# Breakout.net
KiCad netlist of a schematic drawn in EAGLE
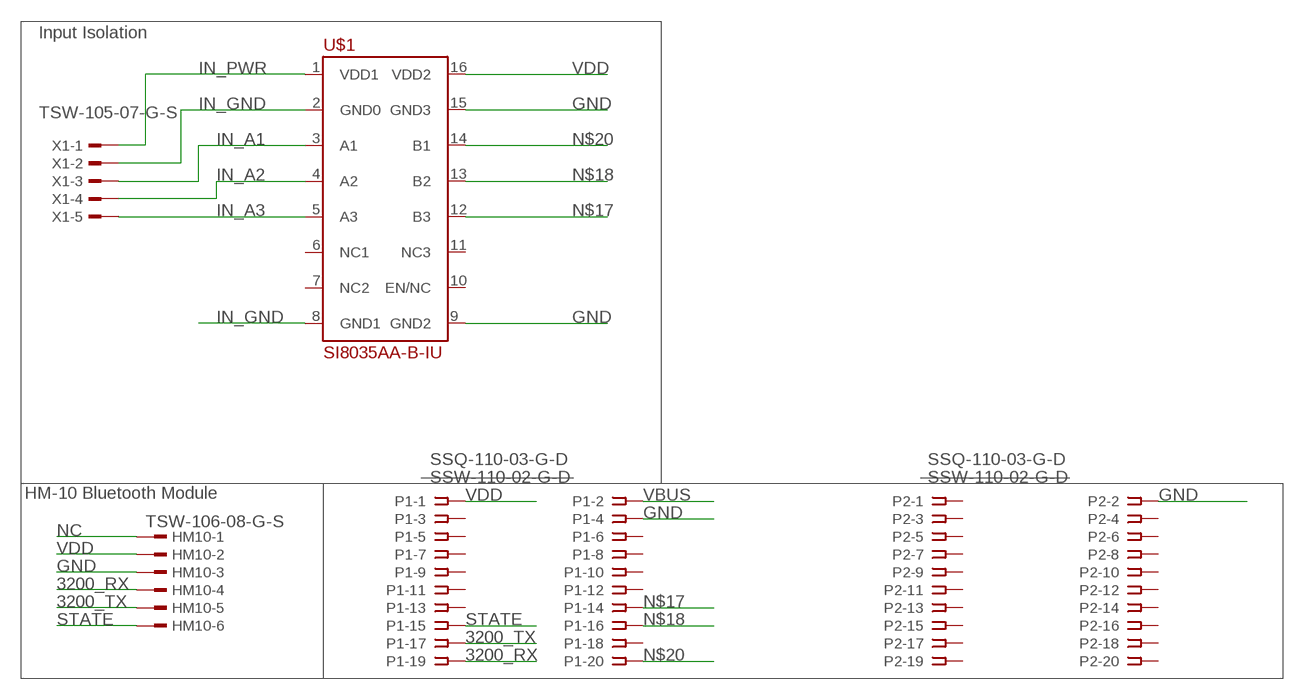
[diagram p0: schematic, sheet 1]

(export (version "E")
  (design (tool "Eeschema 10.0.6"))
  (components
    (comp (ref "HM10")
      (value "TSW-106-08-G-S")
      (footprint "eagle-import:TSW-106-XX-G-S")
      (fields (field (name "MF") "Samtec Inc.") (field (name "MPN") "TSW-106-07-G-S"))
      (libsource (lib "eagle-import") (part "TSW-106--G-S08"))
    )
    (comp (ref "P1")
      (value "SSW-110-02-G-D")
      (footprint "eagle-import:SSW-110-02-G-D")
      (fields (field (name "MF") "Samtec Inc."))
      (libsource (lib "eagle-import") (part "SSW-110-02-G-D"))
    )
    (comp (ref "P2")
      (value "SSW-110-02-G-D")
      (footprint "eagle-import:SSW-110-02-G-D")
      (fields (field (name "MF") "Samtec Inc."))
      (libsource (lib "eagle-import") (part "SSW-110-02-G-D"))
    )
    (comp (ref "U$1")
      (value "SI8035AA-B-IU")
      (footprint "eagle-import:SOP63P602X175-16N")
      (libsource (lib "eagle-import") (part "SI8035AA-B-IU"))
    )
    (comp (ref "X1")
      (value "TSW-105-07-G-S")
      (footprint "eagle-import:TSW-105-XX-G-S")
      (fields (field (name "MF") "Samtec Inc."))
      (libsource (lib "eagle-import") (part "TSW-105--G-S07"))
    )
  )
  (nets
    (net (code "1") (name "/3200_RX") (class "Default")
      (node (ref "HM10") (pin "4") (pinfunction "1_4") (pintype "passive"))
      (node (ref "P1") (pin "19") (pinfunction "1_19") (pintype "passive"))
    )
    (net (code "2") (name "/3200_TX") (class "Default")
      (node (ref "HM10") (pin "5") (pinfunction "1_5") (pintype "passive"))
      (node (ref "P1") (pin "17") (pinfunction "1_17") (pintype "passive"))
    )
    (net (code "3") (name "/GND") (class "Default")
      (node (ref "HM10") (pin "3") (pinfunction "1_3") (pintype "passive"))
      (node (ref "P1") (pin "4") (pinfunction "1_4") (pintype "passive"))
      (node (ref "P2") (pin "2") (pinfunction "1_2") (pintype "passive"))
      (node (ref "U$1") (pin "15") (pinfunction "GND3_15") (pintype "power_in"))
      (node (ref "U$1") (pin "9") (pinfunction "GND2_9") (pintype "power_in"))
    )
    (net (code "4") (name "/IN_A1") (class "Default")
      (node (ref "U$1") (pin "3") (pinfunction "A1_3") (pintype "input"))
      (node (ref "X1") (pin "3") (pinfunction "1_3") (pintype "passive"))
    )
    (net (code "5") (name "/IN_A2") (class "Default")
      (node (ref "U$1") (pin "4") (pinfunction "A2_4") (pintype "input"))
      (node (ref "X1") (pin "4") (pinfunction "1_4") (pintype "passive"))
    )
    (net (code "6") (name "/IN_A3") (class "Default")
      (node (ref "U$1") (pin "5") (pinfunction "A3_5") (pintype "input"))
      (node (ref "X1") (pin "5") (pinfunction "1_5") (pintype "passive"))
    )
    (net (code "7") (name "/IN_GND") (class "Default")
      (node (ref "U$1") (pin "2") (pinfunction "GND0_2") (pintype "power_in"))
      (node (ref "U$1") (pin "8") (pinfunction "GND1_8") (pintype "power_in"))
      (node (ref "X1") (pin "2") (pinfunction "1_2") (pintype "passive"))
    )
    (net (code "8") (name "/IN_PWR") (class "Default")
      (node (ref "U$1") (pin "1") (pinfunction "VDD1_1") (pintype "power_in"))
      (node (ref "X1") (pin "1") (pinfunction "1_1") (pintype "passive"))
    )
    (net (code "9") (name "/N$17") (class "Default")
      (node (ref "P1") (pin "14") (pinfunction "1_14") (pintype "passive"))
      (node (ref "U$1") (pin "12") (pinfunction "B3_12") (pintype "output"))
    )
    (net (code "10") (name "/N$18") (class "Default")
      (node (ref "P1") (pin "16") (pinfunction "1_16") (pintype "passive"))
      (node (ref "U$1") (pin "13") (pinfunction "B2_13") (pintype "output"))
    )
    (net (code "11") (name "/N$20") (class "Default")
      (node (ref "P1") (pin "20") (pinfunction "1_20") (pintype "passive"))
      (node (ref "U$1") (pin "14") (pinfunction "B1_14") (pintype "output"))
    )
    (net (code "12") (name "/NC") (class "Default")
      (node (ref "HM10") (pin "1") (pinfunction "1_1") (pintype "passive"))
    )
    (net (code "13") (name "/STATE") (class "Default")
      (node (ref "HM10") (pin "6") (pinfunction "1_6") (pintype "passive"))
      (node (ref "P1") (pin "15") (pinfunction "1_15") (pintype "passive"))
    )
    (net (code "14") (name "/VBUS") (class "Default")
      (node (ref "P1") (pin "2") (pinfunction "1_2") (pintype "passive"))
    )
    (net (code "15") (name "/VDD") (class "Default")
      (node (ref "HM10") (pin "2") (pinfunction "1_2") (pintype "passive"))
      (node (ref "P1") (pin "1") (pinfunction "1_1") (pintype "passive"))
      (node (ref "U$1") (pin "16") (pinfunction "VDD2_16") (pintype "power_in"))
    )
    (net (code "16") (name "unconnected-(P1B-1-Pad10)") (class "Default")
      (node (ref "P1") (pin "10") (pinfunction "1_10") (pintype "passive"))
    )
    (net (code "17") (name "unconnected-(P1C-1-Pad11)") (class "Default")
      (node (ref "P1") (pin "11") (pinfunction "1_11") (pintype "passive"))
    )
    (net (code "18") (name "unconnected-(P1D-1-Pad12)") (class "Default")
      (node (ref "P1") (pin "12") (pinfunction "1_12") (pintype "passive"))
    )
    (net (code "19") (name "unconnected-(P1E-1-Pad13)") (class "Default")
      (node (ref "P1") (pin "13") (pinfunction "1_13") (pintype "passive"))
    )
    (net (code "20") (name "unconnected-(P1J-1-Pad18)") (class "Default")
      (node (ref "P1") (pin "18") (pinfunction "1_18") (pintype "passive"))
    )
    (net (code "21") (name "unconnected-(P1N-1-Pad3)") (class "Default")
      (node (ref "P1") (pin "3") (pinfunction "1_3") (pintype "passive"))
    )
    (net (code "22") (name "unconnected-(P1P-1-Pad5)") (class "Default")
      (node (ref "P1") (pin "5") (pinfunction "1_5") (pintype "passive"))
    )
    (net (code "23") (name "unconnected-(P1Q-1-Pad6)") (class "Default")
      (node (ref "P1") (pin "6") (pinfunction "1_6") (pintype "passive"))
    )
    (net (code "24") (name "unconnected-(P1R-1-Pad7)") (class "Default")
      (node (ref "P1") (pin "7") (pinfunction "1_7") (pintype "passive"))
    )
    (net (code "25") (name "unconnected-(P1S-1-Pad8)") (class "Default")
      (node (ref "P1") (pin "8") (pinfunction "1_8") (pintype "passive"))
    )
    (net (code "26") (name "unconnected-(P1T-1-Pad9)") (class "Default")
      (node (ref "P1") (pin "9") (pinfunction "1_9") (pintype "passive"))
    )
    (net (code "27") (name "unconnected-(P2-Pad1)") (class "Default")
      (node (ref "P2") (pin "1") (pinfunction "1_1") (pintype "passive"))
    )
    (net (code "28") (name "unconnected-(P2B-1-Pad10)") (class "Default")
      (node (ref "P2") (pin "10") (pinfunction "1_10") (pintype "passive"))
    )
    (net (code "29") (name "unconnected-(P2C-1-Pad11)") (class "Default")
      (node (ref "P2") (pin "11") (pinfunction "1_11") (pintype "passive"))
    )
    (net (code "30") (name "unconnected-(P2D-1-Pad12)") (class "Default")
      (node (ref "P2") (pin "12") (pinfunction "1_12") (pintype "passive"))
    )
    (net (code "31") (name "unconnected-(P2E-1-Pad13)") (class "Default")
      (node (ref "P2") (pin "13") (pinfunction "1_13") (pintype "passive"))
    )
    (net (code "32") (name "unconnected-(P2F-1-Pad14)") (class "Default")
      (node (ref "P2") (pin "14") (pinfunction "1_14") (pintype "passive"))
    )
    (net (code "33") (name "unconnected-(P2G-1-Pad15)") (class "Default")
      (node (ref "P2") (pin "15") (pinfunction "1_15") (pintype "passive"))
    )
    (net (code "34") (name "unconnected-(P2H-1-Pad16)") (class "Default")
      (node (ref "P2") (pin "16") (pinfunction "1_16") (pintype "passive"))
    )
    (net (code "35") (name "unconnected-(P2I-1-Pad17)") (class "Default")
      (node (ref "P2") (pin "17") (pinfunction "1_17") (pintype "passive"))
    )
    (net (code "36") (name "unconnected-(P2J-1-Pad18)") (class "Default")
      (node (ref "P2") (pin "18") (pinfunction "1_18") (pintype "passive"))
    )
    (net (code "37") (name "unconnected-(P2K-1-Pad19)") (class "Default")
      (node (ref "P2") (pin "19") (pinfunction "1_19") (pintype "passive"))
    )
    (net (code "38") (name "unconnected-(P2M-1-Pad20)") (class "Default")
      (node (ref "P2") (pin "20") (pinfunction "1_20") (pintype "passive"))
    )
    (net (code "39") (name "unconnected-(P2N-1-Pad3)") (class "Default")
      (node (ref "P2") (pin "3") (pinfunction "1_3") (pintype "passive"))
    )
    (net (code "40") (name "unconnected-(P2O-1-Pad4)") (class "Default")
      (node (ref "P2") (pin "4") (pinfunction "1_4") (pintype "passive"))
    )
    (net (code "41") (name "unconnected-(P2P-1-Pad5)") (class "Default")
      (node (ref "P2") (pin "5") (pinfunction "1_5") (pintype "passive"))
    )
    (net (code "42") (name "unconnected-(P2Q-1-Pad6)") (class "Default")
      (node (ref "P2") (pin "6") (pinfunction "1_6") (pintype "passive"))
    )
    (net (code "43") (name "unconnected-(P2R-1-Pad7)") (class "Default")
      (node (ref "P2") (pin "7") (pinfunction "1_7") (pintype "passive"))
    )
    (net (code "44") (name "unconnected-(P2S-1-Pad8)") (class "Default")
      (node (ref "P2") (pin "8") (pinfunction "1_8") (pintype "passive"))
    )
    (net (code "45") (name "unconnected-(P2T-1-Pad9)") (class "Default")
      (node (ref "P2") (pin "9") (pinfunction "1_9") (pintype "passive"))
    )
    (net (code "46") (name "unconnected-(U$1-EN{slash}NC-Pad10)") (class "Default")
      (node (ref "U$1") (pin "10") (pinfunction "EN/NC_10") (pintype "no_connect"))
    )
    (net (code "47") (name "unconnected-(U$1-NC1-Pad6)") (class "Default")
      (node (ref "U$1") (pin "6") (pinfunction "NC1_6") (pintype "no_connect"))
    )
    (net (code "48") (name "unconnected-(U$1-NC2-Pad7)") (class "Default")
      (node (ref "U$1") (pin "7") (pinfunction "NC2_7") (pintype "no_connect"))
    )
    (net (code "49") (name "unconnected-(U$1-NC3-Pad11)") (class "Default")
      (node (ref "U$1") (pin "11") (pinfunction "NC3_11") (pintype "no_connect"))
    )
  )
)
